# CortexPrint.net
KiCad netlist of a schematic drawn in EAGLE
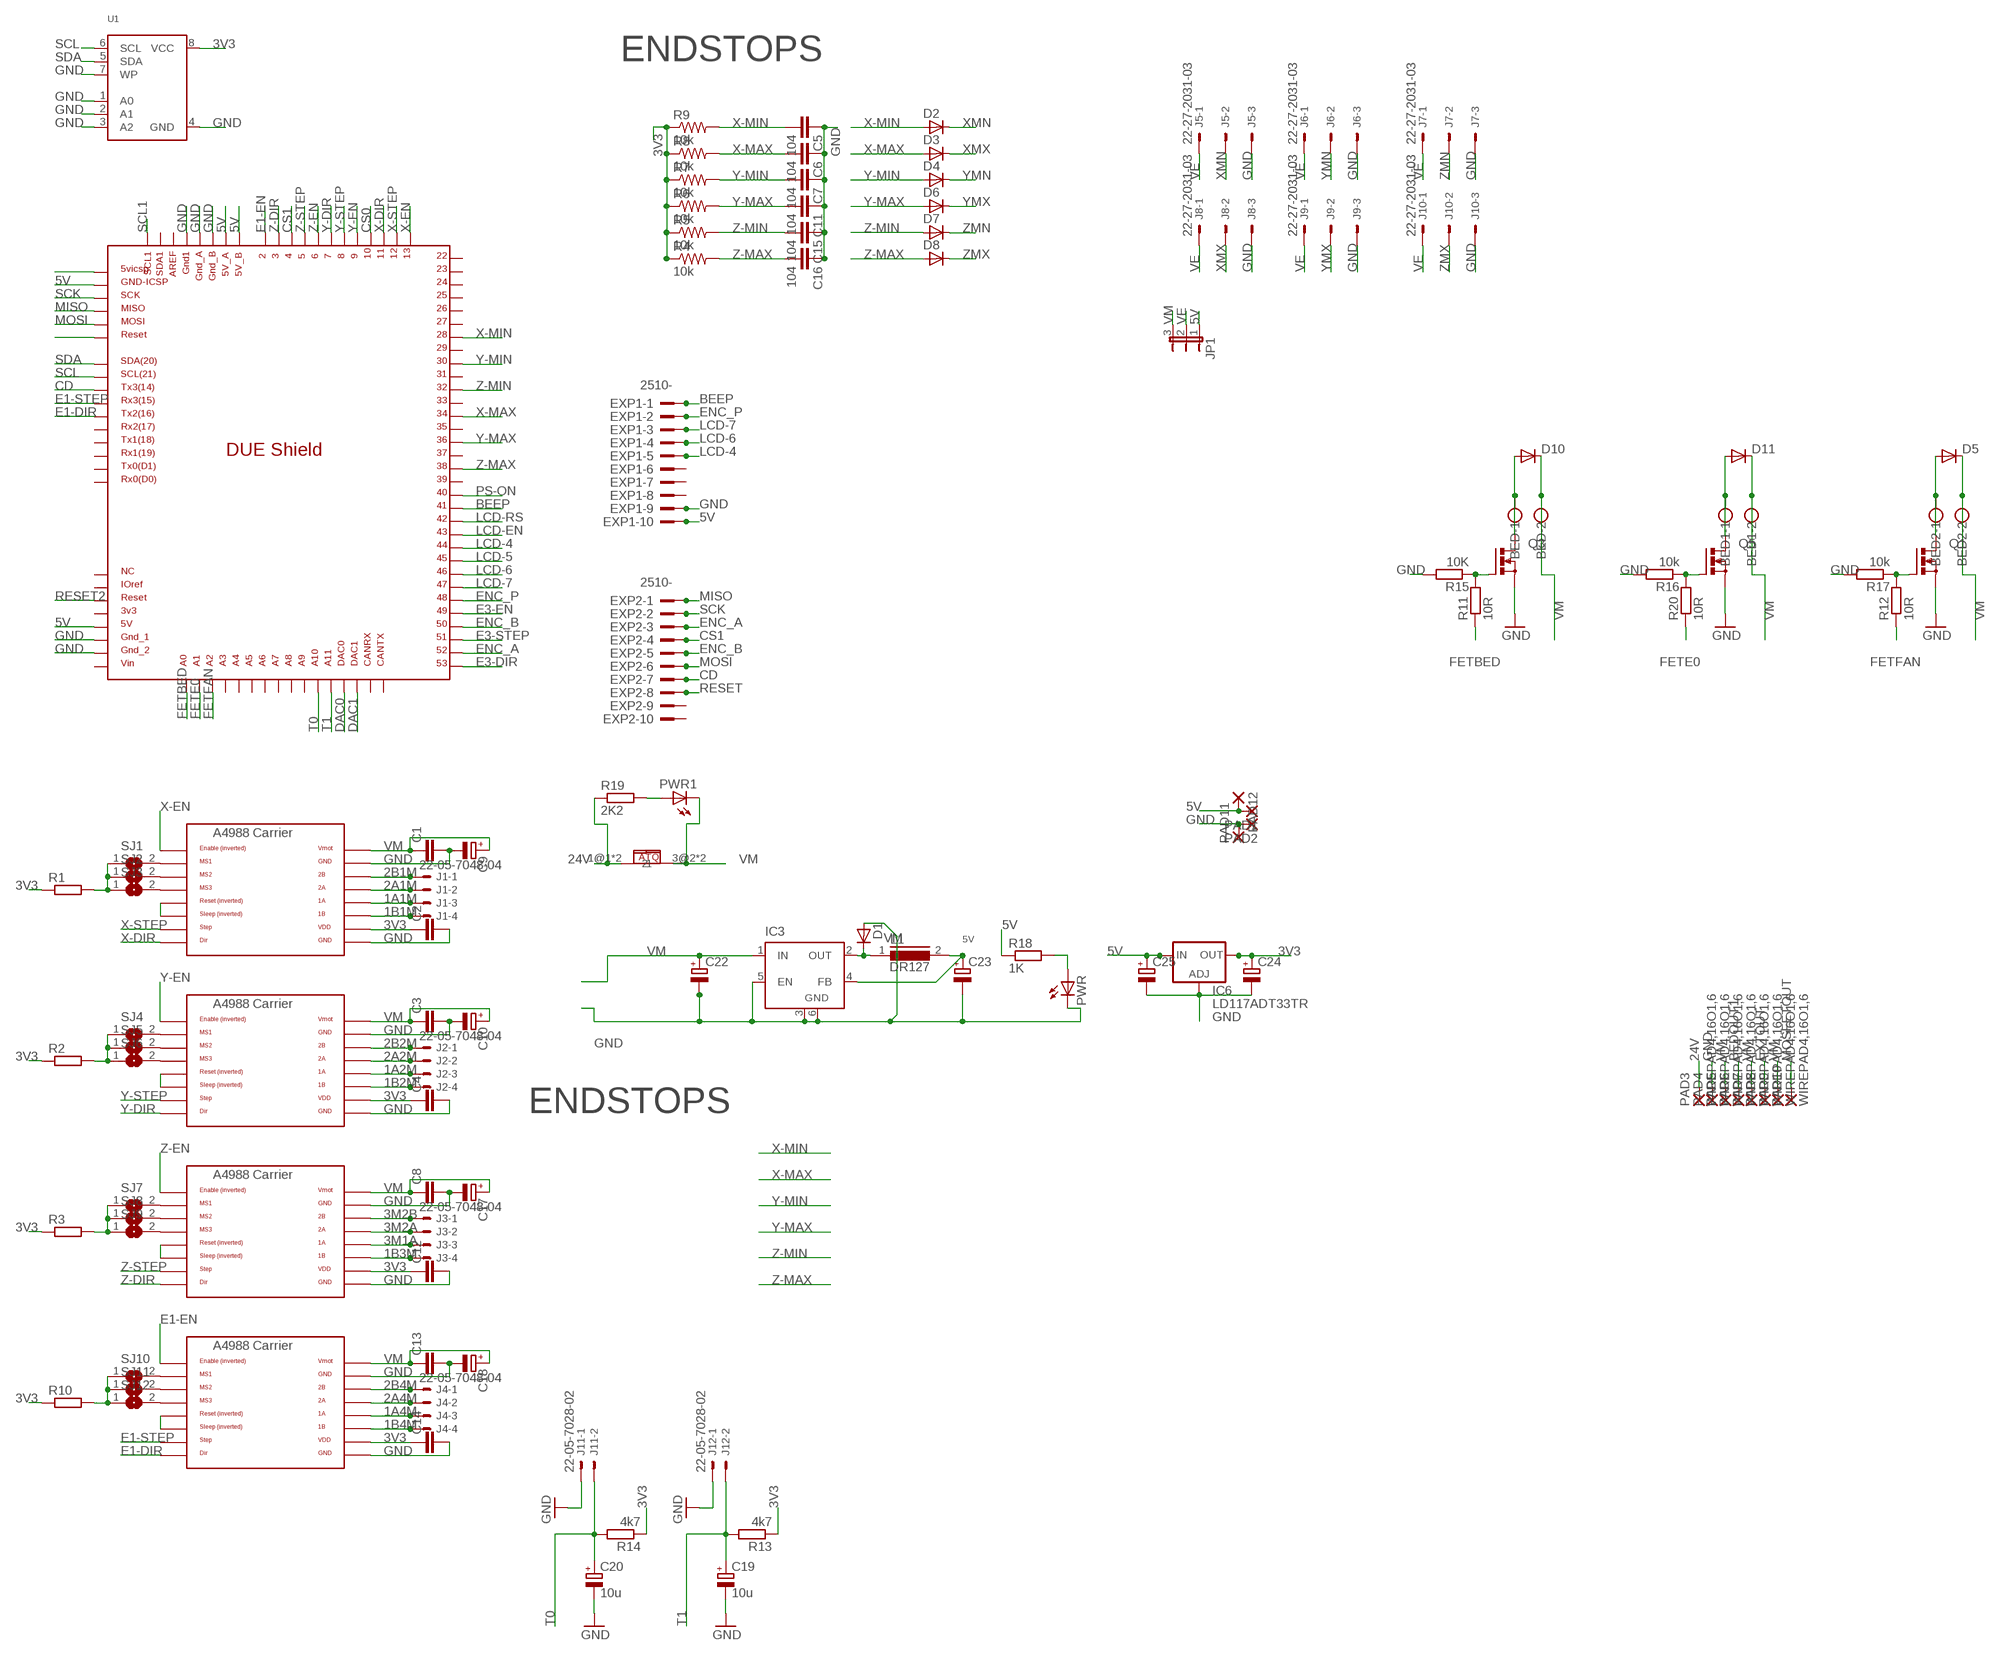
[diagram p0: schematic, sheet 1]

(export (version "E")
  (design (tool "Eeschema 10.0.6"))
  (components
    (comp (ref "BED")
      (value "W237-102")
      (footprint "eagle-import:W237-102")
      (fields (field (name "MPN") "237-102"))
      (libsource (lib "eagle-import") (part "W237-102"))
    )
    (comp (ref "BED1")
      (value "W237-102")
      (footprint "eagle-import:W237-102")
      (fields (field (name "MPN") "237-102"))
      (libsource (lib "eagle-import") (part "W237-102"))
    )
    (comp (ref "BED2")
      (value "W237-102")
      (footprint "eagle-import:W237-102")
      (fields (field (name "MPN") "237-102"))
      (libsource (lib "eagle-import") (part "W237-102"))
    )
    (comp (ref "C1")
      (value "C-EUC1206")
      (footprint "eagle-import:C1206")
      (libsource (lib "eagle-import") (part "C-EUC1206"))
    )
    (comp (ref "C2")
      (value "C-EUC1206")
      (footprint "eagle-import:C1206")
      (libsource (lib "eagle-import") (part "C-EUC1206"))
    )
    (comp (ref "C3")
      (value "C-EUC1206")
      (footprint "eagle-import:C1206")
      (libsource (lib "eagle-import") (part "C-EUC1206"))
    )
    (comp (ref "C4")
      (value "C-EUC1206")
      (footprint "eagle-import:C1206")
      (libsource (lib "eagle-import") (part "C-EUC1206"))
    )
    (comp (ref "C5")
      (value "104")
      (footprint "eagle-import:C1206")
      (libsource (lib "eagle-import") (part "C-EUC1206"))
    )
    (comp (ref "C6")
      (value "104")
      (footprint "eagle-import:C1206")
      (libsource (lib "eagle-import") (part "C-EUC1206"))
    )
    (comp (ref "C7")
      (value "104")
      (footprint "eagle-import:C1206")
      (libsource (lib "eagle-import") (part "C-EUC1206"))
    )
    (comp (ref "C8")
      (value "C-EUC1206")
      (footprint "eagle-import:C1206")
      (libsource (lib "eagle-import") (part "C-EUC1206"))
    )
    (comp (ref "C9")
      (value "CPOL-EUE2,5-6E")
      (footprint "eagle-import:E2,5-6E")
      (libsource (lib "eagle-import") (part "CPOL-EUE2,5-6E"))
    )
    (comp (ref "C10")
      (value "CPOL-EUE2,5-6E")
      (footprint "eagle-import:E2,5-6E")
      (libsource (lib "eagle-import") (part "CPOL-EUE2,5-6E"))
    )
    (comp (ref "C11")
      (value "104")
      (footprint "eagle-import:C1206")
      (libsource (lib "eagle-import") (part "C-EUC1206"))
    )
    (comp (ref "C12")
      (value "C-EUC1206")
      (footprint "eagle-import:C1206")
      (libsource (lib "eagle-import") (part "C-EUC1206"))
    )
    (comp (ref "C13")
      (value "C-EUC1206")
      (footprint "eagle-import:C1206")
      (libsource (lib "eagle-import") (part "C-EUC1206"))
    )
    (comp (ref "C14")
      (value "C-EUC1206")
      (footprint "eagle-import:C1206")
      (libsource (lib "eagle-import") (part "C-EUC1206"))
    )
    (comp (ref "C15")
      (value "104")
      (footprint "eagle-import:C1206")
      (libsource (lib "eagle-import") (part "C-EUC1206"))
    )
    (comp (ref "C16")
      (value "104")
      (footprint "eagle-import:C1206")
      (libsource (lib "eagle-import") (part "C-EUC1206"))
    )
    (comp (ref "C17")
      (value "CPOL-EUE2,5-6E")
      (footprint "eagle-import:E2,5-6E")
      (libsource (lib "eagle-import") (part "CPOL-EUE2,5-6E"))
    )
    (comp (ref "C18")
      (value "CPOL-EUE2,5-6E")
      (footprint "eagle-import:E2,5-6E")
      (libsource (lib "eagle-import") (part "CPOL-EUE2,5-6E"))
    )
    (comp (ref "C19")
      (value "10u")
      (footprint "eagle-import:SANYO-OSCON_SMD_B6")
      (libsource (lib "eagle-import") (part "CPOL-EUSANYO_SMD_B6"))
    )
    (comp (ref "C20")
      (value "10u")
      (footprint "eagle-import:SANYO-OSCON_SMD_B6")
      (libsource (lib "eagle-import") (part "CPOL-EUSANYO_SMD_B6"))
    )
    (comp (ref "C22")
      (value "CPOL-EUE")
      (footprint "eagle-import:PANASONIC_E")
      (libsource (lib "eagle-import") (part "resistor_CPOL-EUE"))
    )
    (comp (ref "C23")
      (value "CPOL-EUE")
      (footprint "eagle-import:PANASONIC_E")
      (libsource (lib "eagle-import") (part "resistor_CPOL-EUE"))
    )
    (comp (ref "C24")
      (value "CPOL-EUD")
      (footprint "eagle-import:PANASONIC_D")
      (libsource (lib "eagle-import") (part "CPOL-EUD"))
    )
    (comp (ref "C25")
      (value "CPOL-EUD")
      (footprint "eagle-import:PANASONIC_D")
      (libsource (lib "eagle-import") (part "CPOL-EUD"))
    )
    (comp (ref "D1")
      (value "D-SOD-87")
      (footprint "eagle-import:SOD87")
      (libsource (lib "eagle-import") (part "D-SOD-87"))
    )
    (comp (ref "D2")
      (value "D-SOD-87")
      (footprint "eagle-import:SOD87")
      (libsource (lib "eagle-import") (part "D-SOD-87"))
    )
    (comp (ref "D3")
      (value "D-SOD-87")
      (footprint "eagle-import:SOD87")
      (libsource (lib "eagle-import") (part "D-SOD-87"))
    )
    (comp (ref "D4")
      (value "D-SOD-87")
      (footprint "eagle-import:SOD87")
      (libsource (lib "eagle-import") (part "D-SOD-87"))
    )
    (comp (ref "D5")
      (value "DIODESMA-ALT")
      (footprint "eagle-import:SMA-DIODE_ALT")
      (libsource (lib "eagle-import") (part "DIODESMA-ALT"))
    )
    (comp (ref "D6")
      (value "D-SOD-87")
      (footprint "eagle-import:SOD87")
      (libsource (lib "eagle-import") (part "D-SOD-87"))
    )
    (comp (ref "D7")
      (value "D-SOD-87")
      (footprint "eagle-import:SOD87")
      (libsource (lib "eagle-import") (part "D-SOD-87"))
    )
    (comp (ref "D8")
      (value "D-SOD-87")
      (footprint "eagle-import:SOD87")
      (libsource (lib "eagle-import") (part "D-SOD-87"))
    )
    (comp (ref "D10")
      (value "DIODESMA-ALT")
      (footprint "eagle-import:SMA-DIODE_ALT")
      (libsource (lib "eagle-import") (part "DIODESMA-ALT"))
    )
    (comp (ref "D11")
      (value "DIODESMA-ALT")
      (footprint "eagle-import:SMA-DIODE_ALT")
      (libsource (lib "eagle-import") (part "DIODESMA-ALT"))
    )
    (comp (ref "EXP1")
      (value "2510-")
      (footprint "eagle-import:PAK100_2500-10")
      (fields (field (name "MF") "3M") (field (name "MPN") "2510-6002UB"))
      (libsource (lib "eagle-import") (part "2510-"))
    )
    (comp (ref "EXP2")
      (value "2510-")
      (footprint "eagle-import:PAK100_2500-10")
      (fields (field (name "MF") "3M") (field (name "MPN") "2510-6002UB"))
      (libsource (lib "eagle-import") (part "2510-"))
    )
    (comp (ref "IC3")
      (value "LM2596S")
      (footprint "eagle-import:TO263-5")
      (libsource (lib "eagle-import") (part "LM2596S"))
    )
    (comp (ref "IC6")
      (value "LD117ADT33TR")
      (footprint "eagle-import:DPACK")
      (libsource (lib "eagle-import") (part "LD117A?DT33TR"))
    )
    (comp (ref "J1")
      (value "22-05-7048-04")
      (footprint "eagle-import:7395-04")
      (libsource (lib "eagle-import") (part "22-?-0405-7048"))
    )
    (comp (ref "J2")
      (value "22-05-7048-04")
      (footprint "eagle-import:7395-04")
      (libsource (lib "eagle-import") (part "22-?-0405-7048"))
    )
    (comp (ref "J3")
      (value "22-05-7048-04")
      (footprint "eagle-import:7395-04")
      (libsource (lib "eagle-import") (part "22-?-0405-7048"))
    )
    (comp (ref "J4")
      (value "22-05-7048-04")
      (footprint "eagle-import:7395-04")
      (libsource (lib "eagle-import") (part "22-?-0405-7048"))
    )
    (comp (ref "J5")
      (value "22-27-2031-03")
      (footprint "eagle-import:6410-03")
      (libsource (lib "eagle-import") (part "22-?-0327-2031"))
    )
    (comp (ref "J6")
      (value "22-27-2031-03")
      (footprint "eagle-import:6410-03")
      (libsource (lib "eagle-import") (part "22-?-0327-2031"))
    )
    (comp (ref "J7")
      (value "22-27-2031-03")
      (footprint "eagle-import:6410-03")
      (libsource (lib "eagle-import") (part "22-?-0327-2031"))
    )
    (comp (ref "J8")
      (value "22-27-2031-03")
      (footprint "eagle-import:6410-03")
      (libsource (lib "eagle-import") (part "22-?-0327-2031"))
    )
    (comp (ref "J9")
      (value "22-27-2031-03")
      (footprint "eagle-import:6410-03")
      (libsource (lib "eagle-import") (part "22-?-0327-2031"))
    )
    (comp (ref "J10")
      (value "22-27-2031-03")
      (footprint "eagle-import:6410-03")
      (libsource (lib "eagle-import") (part "22-?-0327-2031"))
    )
    (comp (ref "J11")
      (value "22-05-7028-02")
      (footprint "eagle-import:7395-02")
      (libsource (lib "eagle-import") (part "22-?-0205-7028"))
    )
    (comp (ref "J12")
      (value "22-05-7028-02")
      (footprint "eagle-import:7395-02")
      (libsource (lib "eagle-import") (part "22-?-0205-7028"))
    )
    (comp (ref "JP1")
      (value "JP2E")
      (footprint "eagle-import:JP2")
      (libsource (lib "eagle-import") (part "JP2E"))
    )
    (comp (ref "L1")
      (value "DR127")
      (footprint "eagle-import:DR127")
      (libsource (lib "eagle-import") (part "DR127"))
    )
    (comp (ref "PAD1")
      (value "3,81/1,4")
      (footprint "eagle-import:3,81_1,4")
      (libsource (lib "eagle-import") (part "3,81/1,4"))
    )
    (comp (ref "PAD2")
      (value "3,81/1,4")
      (footprint "eagle-import:3,81_1,4")
      (libsource (lib "eagle-import") (part "3,81/1,4"))
    )
    (comp (ref "PAD3")
      (value "WIREPAD4,16O1,6")
      (footprint "eagle-import:4,16O1,6")
      (libsource (lib "eagle-import") (part "WIREPAD4,16O1,6"))
    )
    (comp (ref "PAD4")
      (value "WIREPAD4,16O1,6")
      (footprint "eagle-import:4,16O1,6")
      (libsource (lib "eagle-import") (part "WIREPAD4,16O1,6"))
    )
    (comp (ref "PAD5")
      (value "WIREPAD4,16O1,6")
      (footprint "eagle-import:4,16O1,6")
      (libsource (lib "eagle-import") (part "WIREPAD4,16O1,6"))
    )
    (comp (ref "PAD6")
      (value "WIREPAD4,16O1,6")
      (footprint "eagle-import:4,16O1,6")
      (libsource (lib "eagle-import") (part "WIREPAD4,16O1,6"))
    )
    (comp (ref "PAD7")
      (value "WIREPAD4,16O1,6")
      (footprint "eagle-import:4,16O1,6")
      (libsource (lib "eagle-import") (part "WIREPAD4,16O1,6"))
    )
    (comp (ref "PAD8")
      (value "WIREPAD4,16O1,6")
      (footprint "eagle-import:4,16O1,6")
      (libsource (lib "eagle-import") (part "WIREPAD4,16O1,6"))
    )
    (comp (ref "PAD9")
      (value "WIREPAD4,16O1,6")
      (footprint "eagle-import:4,16O1,6")
      (libsource (lib "eagle-import") (part "WIREPAD4,16O1,6"))
    )
    (comp (ref "PAD10")
      (value "WIREPAD4,16O1,6")
      (footprint "eagle-import:4,16O1,6")
      (libsource (lib "eagle-import") (part "WIREPAD4,16O1,6"))
    )
    (comp (ref "PAD11")
      (value "3,81/1,4")
      (footprint "eagle-import:3,81_1,4")
      (libsource (lib "eagle-import") (part "3,81/1,4"))
    )
    (comp (ref "PAD12")
      (value "3,81/1,4")
      (footprint "eagle-import:3,81_1,4")
      (libsource (lib "eagle-import") (part "3,81/1,4"))
    )
    (comp (ref "PWR")
      (value "LEDCHIPLED_1206")
      (footprint "eagle-import:CHIPLED_1206")
      (libsource (lib "eagle-import") (part "LEDCHIPLED_1206"))
    )
    (comp (ref "PWR1")
      (value "LEDCHIPLED_1206")
      (footprint "eagle-import:CHIPLED_1206")
      (libsource (lib "eagle-import") (part "LEDCHIPLED_1206"))
    )
    (comp (ref "Q1")
      (value "PMOSFET_NTO220BV")
      (footprint "eagle-import:TO220BV")
      (libsource (lib "eagle-import") (part "PMOSFET_NTO220BV"))
    )
    (comp (ref "Q3")
      (value "PMOSFET_NTO220BV")
      (footprint "eagle-import:TO220BV")
      (libsource (lib "eagle-import") (part "PMOSFET_NTO220BV"))
    )
    (comp (ref "Q5")
      (value "PMOSFET_NTO220BV")
      (footprint "eagle-import:TO220BV")
      (libsource (lib "eagle-import") (part "PMOSFET_NTO220BV"))
    )
    (comp (ref "R1")
      (value "R-EU_0207/7")
      (footprint "eagle-import:0207_7")
      (libsource (lib "eagle-import") (part "R-EU_0207/7"))
    )
    (comp (ref "R2")
      (value "R-EU_0204/7")
      (footprint "eagle-import:0204_7")
      (libsource (lib "eagle-import") (part "R-EU_0204/7"))
    )
    (comp (ref "R3")
      (value "R-EU_0207/7")
      (footprint "eagle-import:0207_7")
      (libsource (lib "eagle-import") (part "R-EU_0207/7"))
    )
    (comp (ref "R4")
      (value "10k")
      (footprint "eagle-import:M1206")
      (libsource (lib "eagle-import") (part "R-US_M1206"))
    )
    (comp (ref "R5")
      (value "10k")
      (footprint "eagle-import:M1206")
      (libsource (lib "eagle-import") (part "R-US_M1206"))
    )
    (comp (ref "R6")
      (value "10k")
      (footprint "eagle-import:M1206")
      (libsource (lib "eagle-import") (part "R-US_M1206"))
    )
    (comp (ref "R7")
      (value "10k")
      (footprint "eagle-import:M1206")
      (libsource (lib "eagle-import") (part "R-US_M1206"))
    )
    (comp (ref "R8")
      (value "10k")
      (footprint "eagle-import:M1206")
      (libsource (lib "eagle-import") (part "R-US_M1206"))
    )
    (comp (ref "R9")
      (value "10k")
      (footprint "eagle-import:M1206")
      (libsource (lib "eagle-import") (part "R-US_M1206"))
    )
    (comp (ref "R10")
      (value "R-EU_0207/7")
      (footprint "eagle-import:0207_7")
      (libsource (lib "eagle-import") (part "R-EU_0207/7"))
    )
    (comp (ref "R11")
      (value "10R")
      (footprint "eagle-import:M1206")
      (libsource (lib "eagle-import") (part "resistor_R-EU_M1206"))
    )
    (comp (ref "R12")
      (value "10R")
      (footprint "eagle-import:M1206")
      (libsource (lib "eagle-import") (part "resistor_R-EU_M1206"))
    )
    (comp (ref "R13")
      (value "4k7")
      (footprint "eagle-import:M1206")
      (libsource (lib "eagle-import") (part "resistor_R-EU_M1206"))
    )
    (comp (ref "R14")
      (value "4k7")
      (footprint "eagle-import:M1206")
      (libsource (lib "eagle-import") (part "resistor_R-EU_M1206"))
    )
    (comp (ref "R15")
      (value "10K")
      (footprint "eagle-import:M1206")
      (libsource (lib "eagle-import") (part "resistor_R-EU_M1206"))
    )
    (comp (ref "R16")
      (value "10k")
      (footprint "eagle-import:M1206")
      (libsource (lib "eagle-import") (part "resistor_R-EU_M1206"))
    )
    (comp (ref "R17")
      (value "10k")
      (footprint "eagle-import:M1206")
      (libsource (lib "eagle-import") (part "resistor_R-EU_M1206"))
    )
    (comp (ref "R18")
      (value "1K")
      (footprint "eagle-import:M1206")
      (libsource (lib "eagle-import") (part "R-EU_M1206"))
    )
    (comp (ref "R19")
      (value "2K2")
      (footprint "eagle-import:M1206")
      (libsource (lib "eagle-import") (part "R-EU_M1206"))
    )
    (comp (ref "R20")
      (value "10R")
      (footprint "eagle-import:M1206")
      (libsource (lib "eagle-import") (part "resistor_R-EU_M1206"))
    )
    (comp (ref "SJ1") (value "SJ") (footprint "eagle-import:SJ") (libsource (lib "eagle-import") (part "SJ")))
    (comp (ref "SJ2") (value "SJ") (footprint "eagle-import:SJ") (libsource (lib "eagle-import") (part "SJ")))
    (comp (ref "SJ3") (value "SJ") (footprint "eagle-import:SJ") (libsource (lib "eagle-import") (part "SJ")))
    (comp (ref "SJ4") (value "SJ") (footprint "eagle-import:SJ") (libsource (lib "eagle-import") (part "SJ")))
    (comp (ref "SJ5") (value "SJ") (footprint "eagle-import:SJ") (libsource (lib "eagle-import") (part "SJ")))
    (comp (ref "SJ6") (value "SJ") (footprint "eagle-import:SJ") (libsource (lib "eagle-import") (part "SJ")))
    (comp (ref "SJ7") (value "SJ") (footprint "eagle-import:SJ") (libsource (lib "eagle-import") (part "SJ")))
    (comp (ref "SJ8") (value "SJ") (footprint "eagle-import:SJ") (libsource (lib "eagle-import") (part "SJ")))
    (comp (ref "SJ9") (value "SJ") (footprint "eagle-import:SJ") (libsource (lib "eagle-import") (part "SJ")))
    (comp (ref "SJ10")
      (value "SJ")
      (footprint "eagle-import:SJ")
      (libsource (lib "eagle-import") (part "SJ"))
    )
    (comp (ref "SJ11")
      (value "SJ")
      (footprint "eagle-import:SJ")
      (libsource (lib "eagle-import") (part "SJ"))
    )
    (comp (ref "SJ12")
      (value "SJ")
      (footprint "eagle-import:SJ")
      (libsource (lib "eagle-import") (part "SJ"))
    )
    (comp (ref "U$1")
      (value "DUE(NORMAL)")
      (footprint "eagle-import:DUE(NORMAL)")
      (libsource (lib "eagle-import") (part "DUE(NORMAL)"))
    )
    (comp (ref "U$2")
      (value "POLOLU_A4983CARRIER")
      (footprint "eagle-import:A4988BREAKOUT")
      (libsource (lib "eagle-import") (part "POLOLU_A4983CARRIER"))
    )
    (comp (ref "U$3")
      (value "POLOLU_A4983CARRIER")
      (footprint "eagle-import:A4988BREAKOUT")
      (libsource (lib "eagle-import") (part "POLOLU_A4983CARRIER"))
    )
    (comp (ref "U$4")
      (value "POLOLU_A4983CARRIER")
      (footprint "eagle-import:A4988BREAKOUT")
      (libsource (lib "eagle-import") (part "POLOLU_A4983CARRIER"))
    )
    (comp (ref "U$5")
      (value "POLOLU_A4983CARRIER")
      (footprint "eagle-import:A4988BREAKOUT")
      (libsource (lib "eagle-import") (part "POLOLU_A4983CARRIER"))
    )
    (comp (ref "U$7")
      (value "CQ-121")
      (footprint "eagle-import:CQ121")
      (libsource (lib "eagle-import") (part "CQ-121"))
    )
    (comp (ref "U1")
      (value "EEPROM_I2C_SOIC8_GENERIC")
      (footprint "eagle-import:SOIC8_150MIL")
      (libsource (lib "eagle-import") (part "EEPROM_I2C_SOIC8_GENERIC"))
    )
  )
  (nets
    (net (code "1") (name "/1A1M") (class "Default")
      (node (ref "J1") (pin "3") (pinfunction "S_3") (pintype "passive"))
      (node (ref "U$2") (pin "1A") (pinfunction "1A_1A") (pintype "output"))
    )
    (net (code "2") (name "/1A2M") (class "Default")
      (node (ref "J2") (pin "3") (pinfunction "S_3") (pintype "passive"))
      (node (ref "U$3") (pin "1A") (pinfunction "1A_1A") (pintype "output"))
    )
    (net (code "3") (name "/1A4M") (class "Default")
      (node (ref "J4") (pin "3") (pinfunction "S_3") (pintype "passive"))
      (node (ref "U$5") (pin "1A") (pinfunction "1A_1A") (pintype "output"))
    )
    (net (code "4") (name "/1B1M") (class "Default")
      (node (ref "J1") (pin "4") (pinfunction "S_4") (pintype "passive"))
      (node (ref "U$2") (pin "1B") (pinfunction "1B_1B") (pintype "output"))
    )
    (net (code "5") (name "/1B2M") (class "Default")
      (node (ref "J2") (pin "4") (pinfunction "S_4") (pintype "passive"))
      (node (ref "U$3") (pin "1B") (pinfunction "1B_1B") (pintype "output"))
    )
    (net (code "6") (name "/1B3M") (class "Default")
      (node (ref "J3") (pin "4") (pinfunction "S_4") (pintype "passive"))
      (node (ref "U$4") (pin "1B") (pinfunction "1B_1B") (pintype "output"))
    )
    (net (code "7") (name "/1B4M") (class "Default")
      (node (ref "J4") (pin "4") (pinfunction "S_4") (pintype "passive"))
      (node (ref "U$5") (pin "1B") (pinfunction "1B_1B") (pintype "output"))
    )
    (net (code "8") (name "/2A1M") (class "Default")
      (node (ref "J1") (pin "2") (pinfunction "S_2") (pintype "passive"))
      (node (ref "U$2") (pin "2A") (pinfunction "2A_2A") (pintype "output"))
    )
    (net (code "9") (name "/2A2M") (class "Default")
      (node (ref "J2") (pin "2") (pinfunction "S_2") (pintype "passive"))
      (node (ref "U$3") (pin "2A") (pinfunction "2A_2A") (pintype "output"))
    )
    (net (code "10") (name "/2A4M") (class "Default")
      (node (ref "J4") (pin "2") (pinfunction "S_2") (pintype "passive"))
      (node (ref "U$5") (pin "2A") (pinfunction "2A_2A") (pintype "output"))
    )
    (net (code "11") (name "/2B1M") (class "Default")
      (node (ref "J1") (pin "1") (pinfunction "S_1") (pintype "passive"))
      (node (ref "U$2") (pin "2B") (pinfunction "2B_2B") (pintype "output"))
    )
    (net (code "12") (name "/2B2M") (class "Default")
      (node (ref "J2") (pin "1") (pinfunction "S_1") (pintype "passive"))
      (node (ref "U$3") (pin "2B") (pinfunction "2B_2B") (pintype "output"))
    )
    (net (code "13") (name "/2B4M") (class "Default")
      (node (ref "J4") (pin "1") (pinfunction "S_1") (pintype "passive"))
      (node (ref "U$5") (pin "2B") (pinfunction "2B_2B") (pintype "output"))
    )
    (net (code "14") (name "/3M1A") (class "Default")
      (node (ref "J3") (pin "3") (pinfunction "S_3") (pintype "passive"))
      (node (ref "U$4") (pin "1A") (pinfunction "1A_1A") (pintype "output"))
    )
    (net (code "15") (name "/3M2A") (class "Default")
      (node (ref "J3") (pin "2") (pinfunction "S_2") (pintype "passive"))
      (node (ref "U$4") (pin "2A") (pinfunction "2A_2A") (pintype "output"))
    )
    (net (code "16") (name "/3M2B") (class "Default")
      (node (ref "J3") (pin "1") (pinfunction "S_1") (pintype "passive"))
      (node (ref "U$4") (pin "2B") (pinfunction "2B_2B") (pintype "output"))
    )
    (net (code "17") (name "/3V3") (class "Default")
      (node (ref "C12") (pin "1") (pinfunction "1_1") (pintype "passive"))
      (node (ref "C14") (pin "1") (pinfunction "1_1") (pintype "passive"))
      (node (ref "C2") (pin "1") (pinfunction "1_1") (pintype "passive"))
      (node (ref "C24") (pin "+") (pinfunction "+_+") (pintype "passive"))
      (node (ref "C4") (pin "1") (pinfunction "1_1") (pintype "passive"))
      (node (ref "IC6") (pin "4") (pinfunction "OUT_4") (pintype "passive"))
      (node (ref "R1") (pin "1") (pinfunction "1_1") (pintype "passive"))
      (node (ref "R10") (pin "1") (pinfunction "1_1") (pintype "passive"))
      (node (ref "R13") (pin "1") (pinfunction "1_1") (pintype "passive"))
      (node (ref "R14") (pin "1") (pinfunction "1_1") (pintype "passive"))
      (node (ref "R2") (pin "1") (pinfunction "1_1") (pintype "passive"))
      (node (ref "R3") (pin "1") (pinfunction "1_1") (pintype "passive"))
      (node (ref "R4") (pin "1") (pinfunction "1_1") (pintype "passive"))
      (node (ref "R5") (pin "1") (pinfunction "1_1") (pintype "passive"))
      (node (ref "R6") (pin "1") (pinfunction "1_1") (pintype "passive"))
      (node (ref "R7") (pin "1") (pinfunction "1_1") (pintype "passive"))
      (node (ref "R8") (pin "1") (pinfunction "1_1") (pintype "passive"))
      (node (ref "R9") (pin "1") (pinfunction "1_1") (pintype "passive"))
      (node (ref "U$2") (pin "VDD") (pinfunction "VDD_VDD") (pintype "power_in"))
      (node (ref "U$3") (pin "VDD") (pinfunction "VDD_VDD") (pintype "power_in"))
      (node (ref "U$4") (pin "VDD") (pinfunction "VDD_VDD") (pintype "power_in"))
      (node (ref "U$5") (pin "VDD") (pinfunction "VDD_VDD") (pintype "power_in"))
      (node (ref "U1") (pin "8") (pinfunction "VCC_8") (pintype "power_in"))
    )
    (net (code "18") (name "/5V") (class "Default")
      (node (ref "C23") (pin "+") (pinfunction "+_+") (pintype "passive"))
      (node (ref "C25") (pin "+") (pinfunction "+_+") (pintype "passive"))
      (node (ref "EXP1") (pin "10") (pinfunction "KL_10") (pintype "passive"))
      (node (ref "IC3") (pin "4") (pinfunction "FB_4") (pintype "input"))
      (node (ref "IC6") (pin "3") (pinfunction "IN_3") (pintype "input"))
      (node (ref "JP1") (pin "1") (pinfunction "1_1") (pintype "passive"))
      (node (ref "L1") (pin "2") (pinfunction "2_2") (pintype "passive"))
      (node (ref "PAD1") (pin "1") (pinfunction "P_1") (pintype "passive"))
      (node (ref "PAD12") (pin "1") (pinfunction "P_1") (pintype "passive"))
      (node (ref "R18") (pin "1") (pinfunction "1_1") (pintype "passive"))
      (node (ref "U$1") (pin "5V-P") (pinfunction "5V_5V-P") (pintype "bidirectional"))
      (node (ref "U$1") (pin "5V_A") (pinfunction "5V_A_5V_A") (pintype "bidirectional"))
      (node (ref "U$1") (pin "5V_B") (pinfunction "5V_B_5V_B") (pintype "bidirectional"))
      (node (ref "U$1") (pin "GND_ICSP") (pinfunction "GND_ICSP_GND_ICSP") (pintype "bidirectional"))
    )
    (net (code "19") (name "/24V") (class "Default")
      (node (ref "PAD3") (pin "1") (pinfunction "P_1") (pintype "passive"))
      (node (ref "R19") (pin "1") (pinfunction "1_1") (pintype "passive"))
      (node (ref "U$7") (pin "1@1") (pinfunction "1_1@1") (pintype "bidirectional"))
      (node (ref "U$7") (pin "2@1") (pinfunction "1_2@1") (pintype "bidirectional"))
    )
    (net (code "20") (name "/BEDOUT1") (class "Default")
      (node (ref "BED") (pin "1") (pinfunction "KL_1") (pintype "passive"))
      (node (ref "D10") (pin "A") (pinfunction "A_A") (pintype "passive"))
      (node (ref "PAD6") (pin "1") (pinfunction "P_1") (pintype "passive"))
      (node (ref "Q3") (pin "D") (pinfunction "D_D") (pintype "passive"))
    )
    (net (code "21") (name "/BEEP") (class "Default")
      (node (ref "EXP1") (pin "1") (pinfunction "KL_1") (pintype "passive"))
      (node (ref "U$1") (pin "41") (pinfunction "41_41") (pintype "bidirectional"))
    )
    (net (code "22") (name "/CD") (class "Default")
      (node (ref "EXP2") (pin "7") (pinfunction "KL_7") (pintype "passive"))
      (node (ref "U$1") (pin "TX3") (pinfunction "TX3_TX3") (pintype "bidirectional"))
    )
    (net (code "23") (name "/CS0") (class "Default")
      (node (ref "U$1") (pin "10") (pinfunction "10_10") (pintype "bidirectional"))
    )
    (net (code "24") (name "/CS1") (class "Default")
      (node (ref "EXP2") (pin "4") (pinfunction "KL_4") (pintype "passive"))
      (node (ref "U$1") (pin "4") (pinfunction "4_4") (pintype "bidirectional"))
    )
    (net (code "25") (name "/DAC0") (class "Default")
      (node (ref "U$1") (pin "DAC0") (pinfunction "DAC0_DAC0") (pintype "bidirectional"))
    )
    (net (code "26") (name "/DAC1") (class "Default")
      (node (ref "U$1") (pin "DAC1") (pinfunction "DAC1_DAC1") (pintype "bidirectional"))
    )
    (net (code "27") (name "/E1-DIR") (class "Default")
      (node (ref "U$1") (pin "TX2") (pinfunction "TX2_TX2") (pintype "bidirectional"))
      (node (ref "U$5") (pin "DIR") (pinfunction "DIR_DIR") (pintype "input"))
    )
    (net (code "28") (name "/E1-EN") (class "Default")
      (node (ref "U$1") (pin "2") (pinfunction "2_2") (pintype "bidirectional"))
      (node (ref "U$5") (pin "EN") (pinfunction "EN_EN") (pintype "input"))
    )
    (net (code "29") (name "/E1-STEP") (class "Default")
      (node (ref "U$1") (pin "RX3") (pinfunction "RX3_RX3") (pintype "bidirectional"))
      (node (ref "U$5") (pin "STEP") (pinfunction "STEP_STEP") (pintype "input"))
    )
    (net (code "30") (name "/E3-DIR") (class "Default")
      (node (ref "U$1") (pin "53") (pinfunction "53_53") (pintype "bidirectional"))
    )
    (net (code "31") (name "/E3-EN") (class "Default")
      (node (ref "U$1") (pin "49") (pinfunction "49_49") (pintype "bidirectional"))
    )
    (net (code "32") (name "/E3-STEP") (class "Default")
      (node (ref "U$1") (pin "51") (pinfunction "51_51") (pintype "bidirectional"))
    )
    (net (code "33") (name "/ENC_A") (class "Default")
      (node (ref "EXP2") (pin "3") (pinfunction "KL_3") (pintype "passive"))
      (node (ref "U$1") (pin "52") (pinfunction "52_52") (pintype "bidirectional"))
    )
    (net (code "34") (name "/ENC_B") (class "Default")
      (node (ref "EXP2") (pin "5") (pinfunction "KL_5") (pintype "passive"))
      (node (ref "U$1") (pin "50") (pinfunction "50_50") (pintype "bidirectional"))
    )
    (net (code "35") (name "/ENC_P") (class "Default")
      (node (ref "EXP1") (pin "2") (pinfunction "KL_2") (pintype "passive"))
      (node (ref "U$1") (pin "48") (pinfunction "48_48") (pintype "bidirectional"))
    )
    (net (code "36") (name "/EXTOUT") (class "Default")
      (node (ref "BED1") (pin "1") (pinfunction "KL_1") (pintype "passive"))
      (node (ref "D11") (pin "A") (pinfunction "A_A") (pintype "passive"))
      (node (ref "PAD8") (pin "1") (pinfunction "P_1") (pintype "passive"))
      (node (ref "Q5") (pin "D") (pinfunction "D_D") (pintype "passive"))
    )
    (net (code "37") (name "/FETBED") (class "Default")
      (node (ref "R11") (pin "1") (pinfunction "1_1") (pintype "passive"))
      (node (ref "U$1") (pin "A0") (pinfunction "A0_A0") (pintype "bidirectional"))
    )
    (net (code "38") (name "/FETE0") (class "Default")
      (node (ref "R20") (pin "1") (pinfunction "1_1") (pintype "passive"))
      (node (ref "U$1") (pin "A1") (pinfunction "A1_A1") (pintype "bidirectional"))
    )
    (net (code "39") (name "/FETFAN") (class "Default")
      (node (ref "R12") (pin "1") (pinfunction "1_1") (pintype "passive"))
      (node (ref "U$1") (pin "A2") (pinfunction "A2_A2") (pintype "bidirectional"))
    )
    (net (code "40") (name "/LCD-4") (class "Default")
      (node (ref "EXP1") (pin "5") (pinfunction "KL_5") (pintype "passive"))
      (node (ref "U$1") (pin "44") (pinfunction "44_44") (pintype "bidirectional"))
    )
    (net (code "41") (name "/LCD-5") (class "Default")
      (node (ref "U$1") (pin "45") (pinfunction "45_45") (pintype "bidirectional"))
    )
    (net (code "42") (name "/LCD-6") (class "Default")
      (node (ref "EXP1") (pin "4") (pinfunction "KL_4") (pintype "passive"))
      (node (ref "U$1") (pin "46") (pinfunction "46_46") (pintype "bidirectional"))
    )
    (net (code "43") (name "/LCD-7") (class "Default")
      (node (ref "EXP1") (pin "3") (pinfunction "KL_3") (pintype "passive"))
      (node (ref "U$1") (pin "47") (pinfunction "47_47") (pintype "bidirectional"))
    )
    (net (code "44") (name "/LCD-EN") (class "Default")
      (node (ref "U$1") (pin "43") (pinfunction "43_43") (pintype "bidirectional"))
    )
    (net (code "45") (name "/LCD-RS") (class "Default")
      (node (ref "U$1") (pin "42") (pinfunction "42_42") (pintype "bidirectional"))
    )
    (net (code "46") (name "/MISO") (class "Default")
      (node (ref "EXP2") (pin "1") (pinfunction "KL_1") (pintype "passive"))
      (node (ref "U$1") (pin "MISO_ICSP") (pinfunction "MISO_ICSP_MISO_ICSP") (pintype "bidirectional"))
    )
    (net (code "47") (name "/MOSFETOUT") (class "Default")
      (node (ref "BED2") (pin "1") (pinfunction "KL_1") (pintype "passive"))
      (node (ref "D5") (pin "A") (pinfunction "A_A") (pintype "passive"))
      (node (ref "PAD10") (pin "1") (pinfunction "P_1") (pintype "passive"))
      (node (ref "Q1") (pin "D") (pinfunction "D_D") (pintype "passive"))
    )
    (net (code "48") (name "/MOSI") (class "Default")
      (node (ref "EXP2") (pin "6") (pinfunction "KL_6") (pintype "passive"))
      (node (ref "U$1") (pin "MOSI_ICSP") (pinfunction "MOSI_ICSP_MOSI_ICSP") (pintype "bidirectional"))
    )
    (net (code "49") (name "/PS-ON") (class "Default")
      (node (ref "U$1") (pin "40") (pinfunction "40_40") (pintype "bidirectional"))
    )
    (net (code "50") (name "/RESET") (class "Default")
      (node (ref "EXP2") (pin "8") (pinfunction "KL_8") (pintype "passive"))
      (node (ref "U$1") (pin "RESET_ICSP") (pinfunction "RESET_ICSP_RESET_ICSP") (pintype "bidirectional"))
    )
    (net (code "51") (name "/RESET2") (class "Default")
      (node (ref "U$1") (pin "RESET") (pinfunction "RESET_RESET") (pintype "bidirectional"))
    )
    (net (code "52") (name "/SCK") (class "Default")
      (node (ref "EXP2") (pin "2") (pinfunction "KL_2") (pintype "passive"))
      (node (ref "U$1") (pin "SCK_ICSP") (pinfunction "SCK_ICSP_SCK_ICSP") (pintype "bidirectional"))
    )
    (net (code "53") (name "/SCL") (class "Default")
      (node (ref "U$1") (pin "SCL") (pinfunction "SCL_SCL") (pintype "bidirectional"))
      (node (ref "U1") (pin "6") (pinfunction "SCL_6") (pintype "input"))
    )
    (net (code "54") (name "/SCL1") (class "Default")
      (node (ref "U$1") (pin "SCL1") (pinfunction "SCL1_SCL1") (pintype "bidirectional"))
    )
    (net (code "55") (name "/SDA") (class "Default")
      (node (ref "U$1") (pin "SDA") (pinfunction "SDA_SDA") (pintype "bidirectional"))
      (node (ref "U1") (pin "5") (pinfunction "SDA_5") (pintype "bidirectional"))
    )
    (net (code "56") (name "/T0") (class "Default")
      (node (ref "C20") (pin "+") (pinfunction "+_+") (pintype "passive"))
      (node (ref "J11") (pin "2") (pinfunction "S_2") (pintype "passive"))
      (node (ref "R14") (pin "2") (pinfunction "2_2") (pintype "passive"))
      (node (ref "U$1") (pin "A10") (pinfunction "A10_A10") (pintype "bidirectional"))
    )
    (net (code "57") (name "/T1") (class "Default")
      (node (ref "C19") (pin "+") (pinfunction "+_+") (pintype "passive"))
      (node (ref "J12") (pin "2") (pinfunction "S_2") (pintype "passive"))
      (node (ref "R13") (pin "2") (pinfunction "2_2") (pintype "passive"))
      (node (ref "U$1") (pin "A11") (pinfunction "A11_A11") (pintype "bidirectional"))
    )
    (net (code "58") (name "/VE") (class "Default")
      (node (ref "J10") (pin "1") (pinfunction "S_1") (pintype "passive"))
      (node (ref "J5") (pin "1") (pinfunction "S_1") (pintype "passive"))
      (node (ref "J6") (pin "1") (pinfunction "S_1") (pintype "passive"))
      (node (ref "J7") (pin "1") (pinfunction "S_1") (pintype "passive"))
      (node (ref "J8") (pin "1") (pinfunction "S_1") (pintype "passive"))
      (node (ref "J9") (pin "1") (pinfunction "S_1") (pintype "passive"))
      (node (ref "JP1") (pin "2") (pinfunction "2_2") (pintype "passive"))
    )
    (net (code "59") (name "/VM") (class "Default")
      (node (ref "BED") (pin "2") (pinfunction "KL_2") (pintype "passive"))
      (node (ref "BED1") (pin "2") (pinfunction "KL_2") (pintype "passive"))
      (node (ref "BED2") (pin "2") (pinfunction "KL_2") (pintype "passive"))
      (node (ref "C1") (pin "1") (pinfunction "1_1") (pintype "passive"))
      (node (ref "C10") (pin "+") (pinfunction "+_+") (pintype "passive"))
      (node (ref "C13") (pin "1") (pinfunction "1_1") (pintype "passive"))
      (node (ref "C17") (pin "+") (pinfunction "+_+") (pintype "passive"))
      (node (ref "C18") (pin "+") (pinfunction "+_+") (pintype "passive"))
      (node (ref "C22") (pin "+") (pinfunction "+_+") (pintype "passive"))
      (node (ref "C3") (pin "1") (pinfunction "1_1") (pintype "passive"))
      (node (ref "C8") (pin "1") (pinfunction "1_1") (pintype "passive"))
      (node (ref "C9") (pin "+") (pinfunction "+_+") (pintype "passive"))
      (node (ref "D10") (pin "C") (pinfunction "C_C") (pintype "passive"))
      (node (ref "D11") (pin "C") (pinfunction "C_C") (pintype "passive"))
      (node (ref "D5") (pin "C") (pinfunction "C_C") (pintype "passive"))
      (node (ref "IC3") (pin "1") (pinfunction "IN_1") (pintype "input"))
      (node (ref "JP1") (pin "3") (pinfunction "3_3") (pintype "passive"))
      (node (ref "PAD5") (pin "1") (pinfunction "P_1") (pintype "passive"))
      (node (ref "PAD7") (pin "1") (pinfunction "P_1") (pintype "passive"))
      (node (ref "PAD9") (pin "1") (pinfunction "P_1") (pintype "passive"))
      (node (ref "PWR1") (pin "C") (pinfunction "C_C") (pintype "passive"))
      (node (ref "U$2") (pin "VMOT") (pinfunction "VMOT_VMOT") (pintype "power_in"))
      (node (ref "U$3") (pin "VMOT") (pinfunction "VMOT_VMOT") (pintype "power_in"))
      (node (ref "U$4") (pin "VMOT") (pinfunction "VMOT_VMOT") (pintype "power_in"))
      (node (ref "U$5") (pin "VMOT") (pinfunction "VMOT_VMOT") (pintype "power_in"))
      (node (ref "U$7") (pin "3@2") (pinfunction "2_3@2") (pintype "bidirectional"))
      (node (ref "U$7") (pin "4@2") (pinfunction "2_4@2") (pintype "bidirectional"))
    )
    (net (code "60") (name "/X-DIR") (class "Default")
      (node (ref "U$1") (pin "11") (pinfunction "11_11") (pintype "bidirectional"))
      (node (ref "U$2") (pin "DIR") (pinfunction "DIR_DIR") (pintype "input"))
    )
    (net (code "61") (name "/X-EN") (class "Default")
      (node (ref "U$1") (pin "13") (pinfunction "13_13") (pintype "bidirectional"))
      (node (ref "U$2") (pin "EN") (pinfunction "EN_EN") (pintype "input"))
    )
    (net (code "62") (name "/X-MAX") (class "Default")
      (node (ref "C6") (pin "2") (pinfunction "2_2") (pintype "passive"))
      (node (ref "D3") (pin "2") (pinfunction "A_2") (pintype "passive"))
      (node (ref "R8") (pin "2") (pinfunction "2_2") (pintype "passive"))
      (node (ref "U$1") (pin "34") (pinfunction "34_34") (pintype "bidirectional"))
    )
    (net (code "63") (name "/X-MIN") (class "Default")
      (node (ref "C5") (pin "2") (pinfunction "2_2") (pintype "passive"))
      (node (ref "D2") (pin "2") (pinfunction "A_2") (pintype "passive"))
      (node (ref "R9") (pin "2") (pinfunction "2_2") (pintype "passive"))
      (node (ref "U$1") (pin "28") (pinfunction "28_28") (pintype "bidirectional"))
    )
    (net (code "64") (name "/X-STEP") (class "Default")
      (node (ref "U$1") (pin "12") (pinfunction "12_12") (pintype "bidirectional"))
      (node (ref "U$2") (pin "STEP") (pinfunction "STEP_STEP") (pintype "input"))
    )
    (net (code "65") (name "/XMN") (class "Default")
      (node (ref "D2") (pin "1") (pinfunction "C_1") (pintype "passive"))
      (node (ref "J5") (pin "2") (pinfunction "S_2") (pintype "passive"))
    )
    (net (code "66") (name "/XMX") (class "Default")
      (node (ref "D3") (pin "1") (pinfunction "C_1") (pintype "passive"))
      (node (ref "J8") (pin "2") (pinfunction "S_2") (pintype "passive"))
    )
    (net (code "67") (name "/Y-DIR") (class "Default")
      (node (ref "U$1") (pin "7") (pinfunction "7_7") (pintype "bidirectional"))
      (node (ref "U$3") (pin "DIR") (pinfunction "DIR_DIR") (pintype "input"))
    )
    (net (code "68") (name "/Y-EN") (class "Default")
      (node (ref "U$1") (pin "9") (pinfunction "9_9") (pintype "bidirectional"))
      (node (ref "U$3") (pin "EN") (pinfunction "EN_EN") (pintype "input"))
    )
    (net (code "69") (name "/Y-MAX") (class "Default")
      (node (ref "C11") (pin "2") (pinfunction "2_2") (pintype "passive"))
      (node (ref "D6") (pin "2") (pinfunction "A_2") (pintype "passive"))
      (node (ref "R6") (pin "2") (pinfunction "2_2") (pintype "passive"))
      (node (ref "U$1") (pin "36") (pinfunction "36_36") (pintype "bidirectional"))
    )
    (net (code "70") (name "/Y-MIN") (class "Default")
      (node (ref "C7") (pin "2") (pinfunction "2_2") (pintype "passive"))
      (node (ref "D4") (pin "2") (pinfunction "A_2") (pintype "passive"))
      (node (ref "R7") (pin "2") (pinfunction "2_2") (pintype "passive"))
      (node (ref "U$1") (pin "30") (pinfunction "30_30") (pintype "bidirectional"))
    )
    (net (code "71") (name "/Y-STEP") (class "Default")
      (node (ref "U$1") (pin "8") (pinfunction "8_8") (pintype "bidirectional"))
      (node (ref "U$3") (pin "STEP") (pinfunction "STEP_STEP") (pintype "input"))
    )
    (net (code "72") (name "/YMN") (class "Default")
      (node (ref "D4") (pin "1") (pinfunction "C_1") (pintype "passive"))
      (node (ref "J6") (pin "2") (pinfunction "S_2") (pintype "passive"))
    )
    (net (code "73") (name "/YMX") (class "Default")
      (node (ref "D6") (pin "1") (pinfunction "C_1") (pintype "passive"))
      (node (ref "J9") (pin "2") (pinfunction "S_2") (pintype "passive"))
    )
    (net (code "74") (name "/Z-DIR") (class "Default")
      (node (ref "U$1") (pin "3") (pinfunction "3_3") (pintype "bidirectional"))
      (node (ref "U$4") (pin "DIR") (pinfunction "DIR_DIR") (pintype "input"))
    )
    (net (code "75") (name "/Z-EN") (class "Default")
      (node (ref "U$1") (pin "6") (pinfunction "6_6") (pintype "bidirectional"))
      (node (ref "U$4") (pin "EN") (pinfunction "EN_EN") (pintype "input"))
    )
    (net (code "76") (name "/Z-MAX") (class "Default")
      (node (ref "C16") (pin "2") (pinfunction "2_2") (pintype "passive"))
      (node (ref "D8") (pin "2") (pinfunction "A_2") (pintype "passive"))
      (node (ref "R4") (pin "2") (pinfunction "2_2") (pintype "passive"))
      (node (ref "U$1") (pin "38") (pinfunction "38_38") (pintype "bidirectional"))
    )
    (net (code "77") (name "/Z-MIN") (class "Default")
      (node (ref "C15") (pin "2") (pinfunction "2_2") (pintype "passive"))
      (node (ref "D7") (pin "2") (pinfunction "A_2") (pintype "passive"))
      (node (ref "R5") (pin "2") (pinfunction "2_2") (pintype "passive"))
      (node (ref "U$1") (pin "32") (pinfunction "32_32") (pintype "bidirectional"))
    )
    (net (code "78") (name "/Z-STEP") (class "Default")
      (node (ref "U$1") (pin "5") (pinfunction "5_5") (pintype "bidirectional"))
      (node (ref "U$4") (pin "STEP") (pinfunction "STEP_STEP") (pintype "input"))
    )
    (net (code "79") (name "/ZMN") (class "Default")
      (node (ref "D7") (pin "1") (pinfunction "C_1") (pintype "passive"))
      (node (ref "J7") (pin "2") (pinfunction "S_2") (pintype "passive"))
    )
    (net (code "80") (name "/ZMX") (class "Default")
      (node (ref "D8") (pin "1") (pinfunction "C_1") (pintype "passive"))
      (node (ref "J10") (pin "2") (pinfunction "S_2") (pintype "passive"))
    )
    (net (code "81") (name "GND") (class "Default")
      (node (ref "C1") (pin "2") (pinfunction "2_2") (pintype "passive"))
      (node (ref "C10") (pin "-") (pinfunction "-_-") (pintype "passive"))
      (node (ref "C11") (pin "1") (pinfunction "1_1") (pintype "passive"))
      (node (ref "C12") (pin "2") (pinfunction "2_2") (pintype "passive"))
      (node (ref "C13") (pin "2") (pinfunction "2_2") (pintype "passive"))
      (node (ref "C14") (pin "2") (pinfunction "2_2") (pintype "passive"))
      (node (ref "C15") (pin "1") (pinfunction "1_1") (pintype "passive"))
      (node (ref "C16") (pin "1") (pinfunction "1_1") (pintype "passive"))
      (node (ref "C17") (pin "-") (pinfunction "-_-") (pintype "passive"))
      (node (ref "C18") (pin "-") (pinfunction "-_-") (pintype "passive"))
      (node (ref "C19") (pin "-") (pinfunction "-_-") (pintype "passive"))
      (node (ref "C2") (pin "2") (pinfunction "2_2") (pintype "passive"))
      (node (ref "C20") (pin "-") (pinfunction "-_-") (pintype "passive"))
      (node (ref "C22") (pin "-") (pinfunction "-_-") (pintype "passive"))
      (node (ref "C23") (pin "-") (pinfunction "-_-") (pintype "passive"))
      (node (ref "C24") (pin "-") (pinfunction "-_-") (pintype "passive"))
      (node (ref "C25") (pin "-") (pinfunction "-_-") (pintype "passive"))
      (node (ref "C3") (pin "2") (pinfunction "2_2") (pintype "passive"))
      (node (ref "C4") (pin "2") (pinfunction "2_2") (pintype "passive"))
      (node (ref "C5") (pin "1") (pinfunction "1_1") (pintype "passive"))
      (node (ref "C6") (pin "1") (pinfunction "1_1") (pintype "passive"))
      (node (ref "C7") (pin "1") (pinfunction "1_1") (pintype "passive"))
      (node (ref "C8") (pin "2") (pinfunction "2_2") (pintype "passive"))
      (node (ref "C9") (pin "-") (pinfunction "-_-") (pintype "passive"))
      (node (ref "D1") (pin "2") (pinfunction "A_2") (pintype "passive"))
      (node (ref "EXP1") (pin "9") (pinfunction "KL_9") (pintype "passive"))
      (node (ref "IC3") (pin "3") (pinfunction "GND_3") (pintype "power_in"))
      (node (ref "IC3") (pin "5") (pinfunction "EN_5") (pintype "input"))
      (node (ref "IC3") (pin "6") (pinfunction "GND_6") (pintype "power_in"))
      (node (ref "IC6") (pin "1") (pinfunction "ADJ_1") (pintype "input"))
      (node (ref "J10") (pin "3") (pinfunction "S_3") (pintype "passive"))
      (node (ref "J11") (pin "1") (pinfunction "S_1") (pintype "passive"))
      (node (ref "J12") (pin "1") (pinfunction "S_1") (pintype "passive"))
      (node (ref "J5") (pin "3") (pinfunction "S_3") (pintype "passive"))
      (node (ref "J6") (pin "3") (pinfunction "S_3") (pintype "passive"))
      (node (ref "J7") (pin "3") (pinfunction "S_3") (pintype "passive"))
      (node (ref "J8") (pin "3") (pinfunction "S_3") (pintype "passive"))
      (node (ref "J9") (pin "3") (pinfunction "S_3") (pintype "passive"))
      (node (ref "PAD11") (pin "1") (pinfunction "P_1") (pintype "passive"))
      (node (ref "PAD2") (pin "1") (pinfunction "P_1") (pintype "passive"))
      (node (ref "PAD4") (pin "1") (pinfunction "P_1") (pintype "passive"))
      (node (ref "PWR") (pin "C") (pinfunction "C_C") (pintype "passive"))
      (node (ref "Q1") (pin "S") (pinfunction "S_S") (pintype "passive"))
      (node (ref "Q3") (pin "S") (pinfunction "S_S") (pintype "passive"))
      (node (ref "Q5") (pin "S") (pinfunction "S_S") (pintype "passive"))
      (node (ref "R15") (pin "2") (pinfunction "2_2") (pintype "passive"))
      (node (ref "R16") (pin "2") (pinfunction "2_2") (pintype "passive"))
      (node (ref "R17") (pin "2") (pinfunction "2_2") (pintype "passive"))
      (node (ref "U$1") (pin "GND1") (pinfunction "GND1_GND1") (pintype "bidirectional"))
      (node (ref "U$1") (pin "GND_1") (pinfunction "GND_1_GND_1") (pintype "bidirectional"))
      (node (ref "U$1") (pin "GND_2") (pinfunction "GND_2_GND_2") (pintype "bidirectional"))
      (node (ref "U$1") (pin "GND_A") (pinfunction "GND_A_GND_A") (pintype "bidirectional"))
      (node (ref "U$1") (pin "GND_B") (pinfunction "GND_B_GND_B") (pintype "bidirectional"))
      (node (ref "U$2") (pin "GND") (pinfunction "GND_GND") (pintype "power_in"))
      (node (ref "U$2") (pin "GND@0") (pinfunction "GND_GND@0") (pintype "power_in"))
      (node (ref "U$3") (pin "GND") (pinfunction "GND_GND") (pintype "power_in"))
      (node (ref "U$3") (pin "GND@0") (pinfunction "GND_GND@0") (pintype "power_in"))
      (node (ref "U$4") (pin "GND") (pinfunction "GND_GND") (pintype "power_in"))
      (node (ref "U$4") (pin "GND@0") (pinfunction "GND_GND@0") (pintype "power_in"))
      (node (ref "U$5") (pin "GND") (pinfunction "GND_GND") (pintype "power_in"))
      (node (ref "U$5") (pin "GND@0") (pinfunction "GND_GND@0") (pintype "power_in"))
      (node (ref "U1") (pin "1") (pinfunction "A0_1") (pintype "input"))
      (node (ref "U1") (pin "2") (pinfunction "A1_2") (pintype "input"))
      (node (ref "U1") (pin "3") (pinfunction "A2_3") (pintype "input"))
      (node (ref "U1") (pin "4") (pinfunction "GND_4") (pintype "power_in"))
      (node (ref "U1") (pin "7") (pinfunction "WP_7") (pintype "input"))
    )
    (net (code "82") (name "Net-(D1-C)") (class "Default")
      (node (ref "D1") (pin "1") (pinfunction "C_1") (pintype "passive"))
      (node (ref "IC3") (pin "2") (pinfunction "OUT_2") (pintype "output"))
      (node (ref "L1") (pin "1") (pinfunction "1_1") (pintype "passive"))
    )
    (net (code "83") (name "Net-(PWR-PadA)") (class "Default")
      (node (ref "PWR") (pin "A") (pinfunction "A_A") (pintype "passive"))
      (node (ref "R18") (pin "2") (pinfunction "2_2") (pintype "passive"))
    )
    (net (code "84") (name "Net-(PWR1-PadA)") (class "Default")
      (node (ref "PWR1") (pin "A") (pinfunction "A_A") (pintype "passive"))
      (node (ref "R19") (pin "2") (pinfunction "2_2") (pintype "passive"))
    )
    (net (code "85") (name "Net-(Q1-PadG)") (class "Default")
      (node (ref "Q1") (pin "G") (pinfunction "G_G") (pintype "passive"))
      (node (ref "R12") (pin "2") (pinfunction "2_2") (pintype "passive"))
      (node (ref "R17") (pin "1") (pinfunction "1_1") (pintype "passive"))
    )
    (net (code "86") (name "Net-(Q3-PadG)") (class "Default")
      (node (ref "Q3") (pin "G") (pinfunction "G_G") (pintype "passive"))
      (node (ref "R11") (pin "2") (pinfunction "2_2") (pintype "passive"))
      (node (ref "R15") (pin "1") (pinfunction "1_1") (pintype "passive"))
    )
    (net (code "87") (name "Net-(Q5-PadG)") (class "Default")
      (node (ref "Q5") (pin "G") (pinfunction "G_G") (pintype "passive"))
      (node (ref "R16") (pin "1") (pinfunction "1_1") (pintype "passive"))
      (node (ref "R20") (pin "2") (pinfunction "2_2") (pintype "passive"))
    )
    (net (code "88") (name "Net-(R1-Pad2)") (class "Default")
      (node (ref "R1") (pin "2") (pinfunction "2_2") (pintype "passive"))
      (node (ref "SJ1") (pin "1") (pinfunction "1_1") (pintype "passive"))
      (node (ref "SJ2") (pin "1") (pinfunction "1_1") (pintype "passive"))
      (node (ref "SJ3") (pin "1") (pinfunction "1_1") (pintype "passive"))
    )
    (net (code "89") (name "Net-(R2-Pad2)") (class "Default")
      (node (ref "R2") (pin "2") (pinfunction "2_2") (pintype "passive"))
      (node (ref "SJ4") (pin "1") (pinfunction "1_1") (pintype "passive"))
      (node (ref "SJ5") (pin "1") (pinfunction "1_1") (pintype "passive"))
      (node (ref "SJ6") (pin "1") (pinfunction "1_1") (pintype "passive"))
    )
    (net (code "90") (name "Net-(R3-Pad2)") (class "Default")
      (node (ref "R3") (pin "2") (pinfunction "2_2") (pintype "passive"))
      (node (ref "SJ7") (pin "1") (pinfunction "1_1") (pintype "passive"))
      (node (ref "SJ8") (pin "1") (pinfunction "1_1") (pintype "passive"))
      (node (ref "SJ9") (pin "1") (pinfunction "1_1") (pintype "passive"))
    )
    (net (code "91") (name "Net-(R10-Pad2)") (class "Default")
      (node (ref "R10") (pin "2") (pinfunction "2_2") (pintype "passive"))
      (node (ref "SJ10") (pin "1") (pinfunction "1_1") (pintype "passive"))
      (node (ref "SJ11") (pin "1") (pinfunction "1_1") (pintype "passive"))
      (node (ref "SJ12") (pin "1") (pinfunction "1_1") (pintype "passive"))
    )
    (net (code "92") (name "Net-(SJ1-Pad2)") (class "Default")
      (node (ref "SJ1") (pin "2") (pinfunction "2_2") (pintype "passive"))
      (node (ref "U$2") (pin "MS1") (pinfunction "MS1_MS1") (pintype "input"))
    )
    (net (code "93") (name "Net-(SJ2-Pad2)") (class "Default")
      (node (ref "SJ2") (pin "2") (pinfunction "2_2") (pintype "passive"))
      (node (ref "U$2") (pin "MS2") (pinfunction "MS2_MS2") (pintype "input"))
    )
    (net (code "94") (name "Net-(SJ3-Pad2)") (class "Default")
      (node (ref "SJ3") (pin "2") (pinfunction "2_2") (pintype "passive"))
      (node (ref "U$2") (pin "MS3") (pinfunction "MS3_MS3") (pintype "input"))
    )
    (net (code "95") (name "Net-(SJ4-Pad2)") (class "Default")
      (node (ref "SJ4") (pin "2") (pinfunction "2_2") (pintype "passive"))
      (node (ref "U$3") (pin "MS1") (pinfunction "MS1_MS1") (pintype "input"))
    )
    (net (code "96") (name "Net-(SJ5-Pad2)") (class "Default")
      (node (ref "SJ5") (pin "2") (pinfunction "2_2") (pintype "passive"))
      (node (ref "U$3") (pin "MS2") (pinfunction "MS2_MS2") (pintype "input"))
    )
    (net (code "97") (name "Net-(SJ6-Pad2)") (class "Default")
      (node (ref "SJ6") (pin "2") (pinfunction "2_2") (pintype "passive"))
      (node (ref "U$3") (pin "MS3") (pinfunction "MS3_MS3") (pintype "input"))
    )
    (net (code "98") (name "Net-(SJ7-Pad2)") (class "Default")
      (node (ref "SJ7") (pin "2") (pinfunction "2_2") (pintype "passive"))
      (node (ref "U$4") (pin "MS1") (pinfunction "MS1_MS1") (pintype "input"))
    )
    (net (code "99") (name "Net-(SJ8-Pad2)") (class "Default")
      (node (ref "SJ8") (pin "2") (pinfunction "2_2") (pintype "passive"))
      (node (ref "U$4") (pin "MS2") (pinfunction "MS2_MS2") (pintype "input"))
    )
    (net (code "100") (name "Net-(SJ9-Pad2)") (class "Default")
      (node (ref "SJ9") (pin "2") (pinfunction "2_2") (pintype "passive"))
      (node (ref "U$4") (pin "MS3") (pinfunction "MS3_MS3") (pintype "input"))
    )
    (net (code "101") (name "Net-(SJ10-Pad2)") (class "Default")
      (node (ref "SJ10") (pin "2") (pinfunction "2_2") (pintype "passive"))
      (node (ref "U$5") (pin "MS1") (pinfunction "MS1_MS1") (pintype "input"))
    )
    (net (code "102") (name "Net-(SJ11-Pad2)") (class "Default")
      (node (ref "SJ11") (pin "2") (pinfunction "2_2") (pintype "passive"))
      (node (ref "U$5") (pin "MS2") (pinfunction "MS2_MS2") (pintype "input"))
    )
    (net (code "103") (name "Net-(SJ12-Pad2)") (class "Default")
      (node (ref "SJ12") (pin "2") (pinfunction "2_2") (pintype "passive"))
      (node (ref "U$5") (pin "MS3") (pinfunction "MS3_MS3") (pintype "input"))
    )
    (net (code "104") (name "Net-(U$2-SLEEP)") (class "Default")
      (node (ref "U$2") (pin "RST") (pinfunction "RST_RST") (pintype "input"))
      (node (ref "U$2") (pin "SLP") (pinfunction "SLEEP_SLP") (pintype "input"))
    )
    (net (code "105") (name "Net-(U$3-SLEEP)") (class "Default")
      (node (ref "U$3") (pin "RST") (pinfunction "RST_RST") (pintype "input"))
      (node (ref "U$3") (pin "SLP") (pinfunction "SLEEP_SLP") (pintype "input"))
    )
    (net (code "106") (name "Net-(U$4-SLEEP)") (class "Default")
      (node (ref "U$4") (pin "RST") (pinfunction "RST_RST") (pintype "input"))
      (node (ref "U$4") (pin "SLP") (pinfunction "SLEEP_SLP") (pintype "input"))
    )
    (net (code "107") (name "Net-(U$5-SLEEP)") (class "Default")
      (node (ref "U$5") (pin "RST") (pinfunction "RST_RST") (pintype "input"))
      (node (ref "U$5") (pin "SLP") (pinfunction "SLEEP_SLP") (pintype "input"))
    )
    (net (code "108") (name "unconnected-(EXP1G-KL-Pad6)") (class "Default")
      (node (ref "EXP1") (pin "6") (pinfunction "KL_6") (pintype "passive"))
    )
    (net (code "109") (name "unconnected-(EXP1H-KL-Pad7)") (class "Default")
      (node (ref "EXP1") (pin "7") (pinfunction "KL_7") (pintype "passive"))
    )
    (net (code "110") (name "unconnected-(EXP1I-KL-Pad8)") (class "Default")
      (node (ref "EXP1") (pin "8") (pinfunction "KL_8") (pintype "passive"))
    )
    (net (code "111") (name "unconnected-(EXP2B-KL-Pad10)") (class "Default")
      (node (ref "EXP2") (pin "10") (pinfunction "KL_10") (pintype "passive"))
    )
    (net (code "112") (name "unconnected-(EXP2J-KL-Pad9)") (class "Default")
      (node (ref "EXP2") (pin "9") (pinfunction "KL_9") (pintype "passive"))
    )
    (net (code "113") (name "unconnected-(U$1-Pad3V3)") (class "Default")
      (node (ref "U$1") (pin "3V3") (pinfunction "3V3_3V3") (pintype "bidirectional"))
    )
    (net (code "114") (name "unconnected-(U$1-Pad5V_ICSP)") (class "Default")
      (node (ref "U$1") (pin "5V_ICSP") (pinfunction "5V_ICSP_5V_ICSP") (pintype "bidirectional"))
    )
    (net (code "115") (name "unconnected-(U$1-Pad22)") (class "Default")
      (node (ref "U$1") (pin "22") (pinfunction "22_22") (pintype "bidirectional"))
    )
    (net (code "116") (name "unconnected-(U$1-Pad23)") (class "Default")
      (node (ref "U$1") (pin "23") (pinfunction "23_23") (pintype "bidirectional"))
    )
    (net (code "117") (name "unconnected-(U$1-Pad24)") (class "Default")
      (node (ref "U$1") (pin "24") (pinfunction "24_24") (pintype "bidirectional"))
    )
    (net (code "118") (name "unconnected-(U$1-Pad25)") (class "Default")
      (node (ref "U$1") (pin "25") (pinfunction "25_25") (pintype "bidirectional"))
    )
    (net (code "119") (name "unconnected-(U$1-Pad26)") (class "Default")
      (node (ref "U$1") (pin "26") (pinfunction "26_26") (pintype "bidirectional"))
    )
    (net (code "120") (name "unconnected-(U$1-Pad27)") (class "Default")
      (node (ref "U$1") (pin "27") (pinfunction "27_27") (pintype "bidirectional"))
    )
    (net (code "121") (name "unconnected-(U$1-Pad29)") (class "Default")
      (node (ref "U$1") (pin "29") (pinfunction "29_29") (pintype "bidirectional"))
    )
    (net (code "122") (name "unconnected-(U$1-Pad31)") (class "Default")
      (node (ref "U$1") (pin "31") (pinfunction "31_31") (pintype "bidirectional"))
    )
    (net (code "123") (name "unconnected-(U$1-Pad33)") (class "Default")
      (node (ref "U$1") (pin "33") (pinfunction "33_33") (pintype "bidirectional"))
    )
    (net (code "124") (name "unconnected-(U$1-Pad35)") (class "Default")
      (node (ref "U$1") (pin "35") (pinfunction "35_35") (pintype "bidirectional"))
    )
    (net (code "125") (name "unconnected-(U$1-Pad37)") (class "Default")
      (node (ref "U$1") (pin "37") (pinfunction "37_37") (pintype "bidirectional"))
    )
    (net (code "126") (name "unconnected-(U$1-Pad39)") (class "Default")
      (node (ref "U$1") (pin "39") (pinfunction "39_39") (pintype "bidirectional"))
    )
    (net (code "127") (name "unconnected-(U$1-PadA3)") (class "Default")
      (node (ref "U$1") (pin "A3") (pinfunction "A3_A3") (pintype "bidirectional"))
    )
    (net (code "128") (name "unconnected-(U$1-PadA4)") (class "Default")
      (node (ref "U$1") (pin "A4") (pinfunction "A4_A4") (pintype "bidirectional"))
    )
    (net (code "129") (name "unconnected-(U$1-PadA5)") (class "Default")
      (node (ref "U$1") (pin "A5") (pinfunction "A5_A5") (pintype "bidirectional"))
    )
    (net (code "130") (name "unconnected-(U$1-PadA6)") (class "Default")
      (node (ref "U$1") (pin "A6") (pinfunction "A6_A6") (pintype "bidirectional"))
    )
    (net (code "131") (name "unconnected-(U$1-PadA7)") (class "Default")
      (node (ref "U$1") (pin "A7") (pinfunction "A7_A7") (pintype "bidirectional"))
    )
    (net (code "132") (name "unconnected-(U$1-PadA8)") (class "Default")
      (node (ref "U$1") (pin "A8") (pinfunction "A8_A8") (pintype "bidirectional"))
    )
    (net (code "133") (name "unconnected-(U$1-PadA9)") (class "Default")
      (node (ref "U$1") (pin "A9") (pinfunction "A9_A9") (pintype "bidirectional"))
    )
    (net (code "134") (name "unconnected-(U$1-PadAREF)") (class "Default")
      (node (ref "U$1") (pin "AREF") (pinfunction "AREF_AREF") (pintype "bidirectional"))
    )
    (net (code "135") (name "unconnected-(U$1-PadCANRX)") (class "Default")
      (node (ref "U$1") (pin "CANRX") (pinfunction "CANRX_CANRX") (pintype "bidirectional"))
    )
    (net (code "136") (name "unconnected-(U$1-PadCANTX)") (class "Default")
      (node (ref "U$1") (pin "CANTX") (pinfunction "CANTX_CANTX") (pintype "bidirectional"))
    )
    (net (code "137") (name "unconnected-(U$1-PadIOREF)") (class "Default")
      (node (ref "U$1") (pin "IOREF") (pinfunction "IOREF_IOREF") (pintype "bidirectional"))
    )
    (net (code "138") (name "unconnected-(U$1-PadNC)") (class "Default")
      (node (ref "U$1") (pin "NC") (pinfunction "NC_NC") (pintype "bidirectional"))
    )
    (net (code "139") (name "unconnected-(U$1-PadRX0)") (class "Default")
      (node (ref "U$1") (pin "RX0") (pinfunction "RX0_RX0") (pintype "bidirectional"))
    )
    (net (code "140") (name "unconnected-(U$1-PadRX1)") (class "Default")
      (node (ref "U$1") (pin "RX1") (pinfunction "RX1_RX1") (pintype "bidirectional"))
    )
    (net (code "141") (name "unconnected-(U$1-PadRX2)") (class "Default")
      (node (ref "U$1") (pin "RX2") (pinfunction "RX2_RX2") (pintype "bidirectional"))
    )
    (net (code "142") (name "unconnected-(U$1-PadSDA1)") (class "Default")
      (node (ref "U$1") (pin "SDA1") (pinfunction "SDA1_SDA1") (pintype "bidirectional"))
    )
    (net (code "143") (name "unconnected-(U$1-PadTX0)") (class "Default")
      (node (ref "U$1") (pin "TX0") (pinfunction "TX0_TX0") (pintype "bidirectional"))
    )
    (net (code "144") (name "unconnected-(U$1-PadTX1)") (class "Default")
      (node (ref "U$1") (pin "TX1") (pinfunction "TX1_TX1") (pintype "bidirectional"))
    )
    (net (code "145") (name "unconnected-(U$1-PadVIN)") (class "Default")
      (node (ref "U$1") (pin "VIN") (pinfunction "VIN_VIN") (pintype "bidirectional"))
    )
  )
)
